# pcb.net
KiCad netlist of a schematic drawn in EAGLE
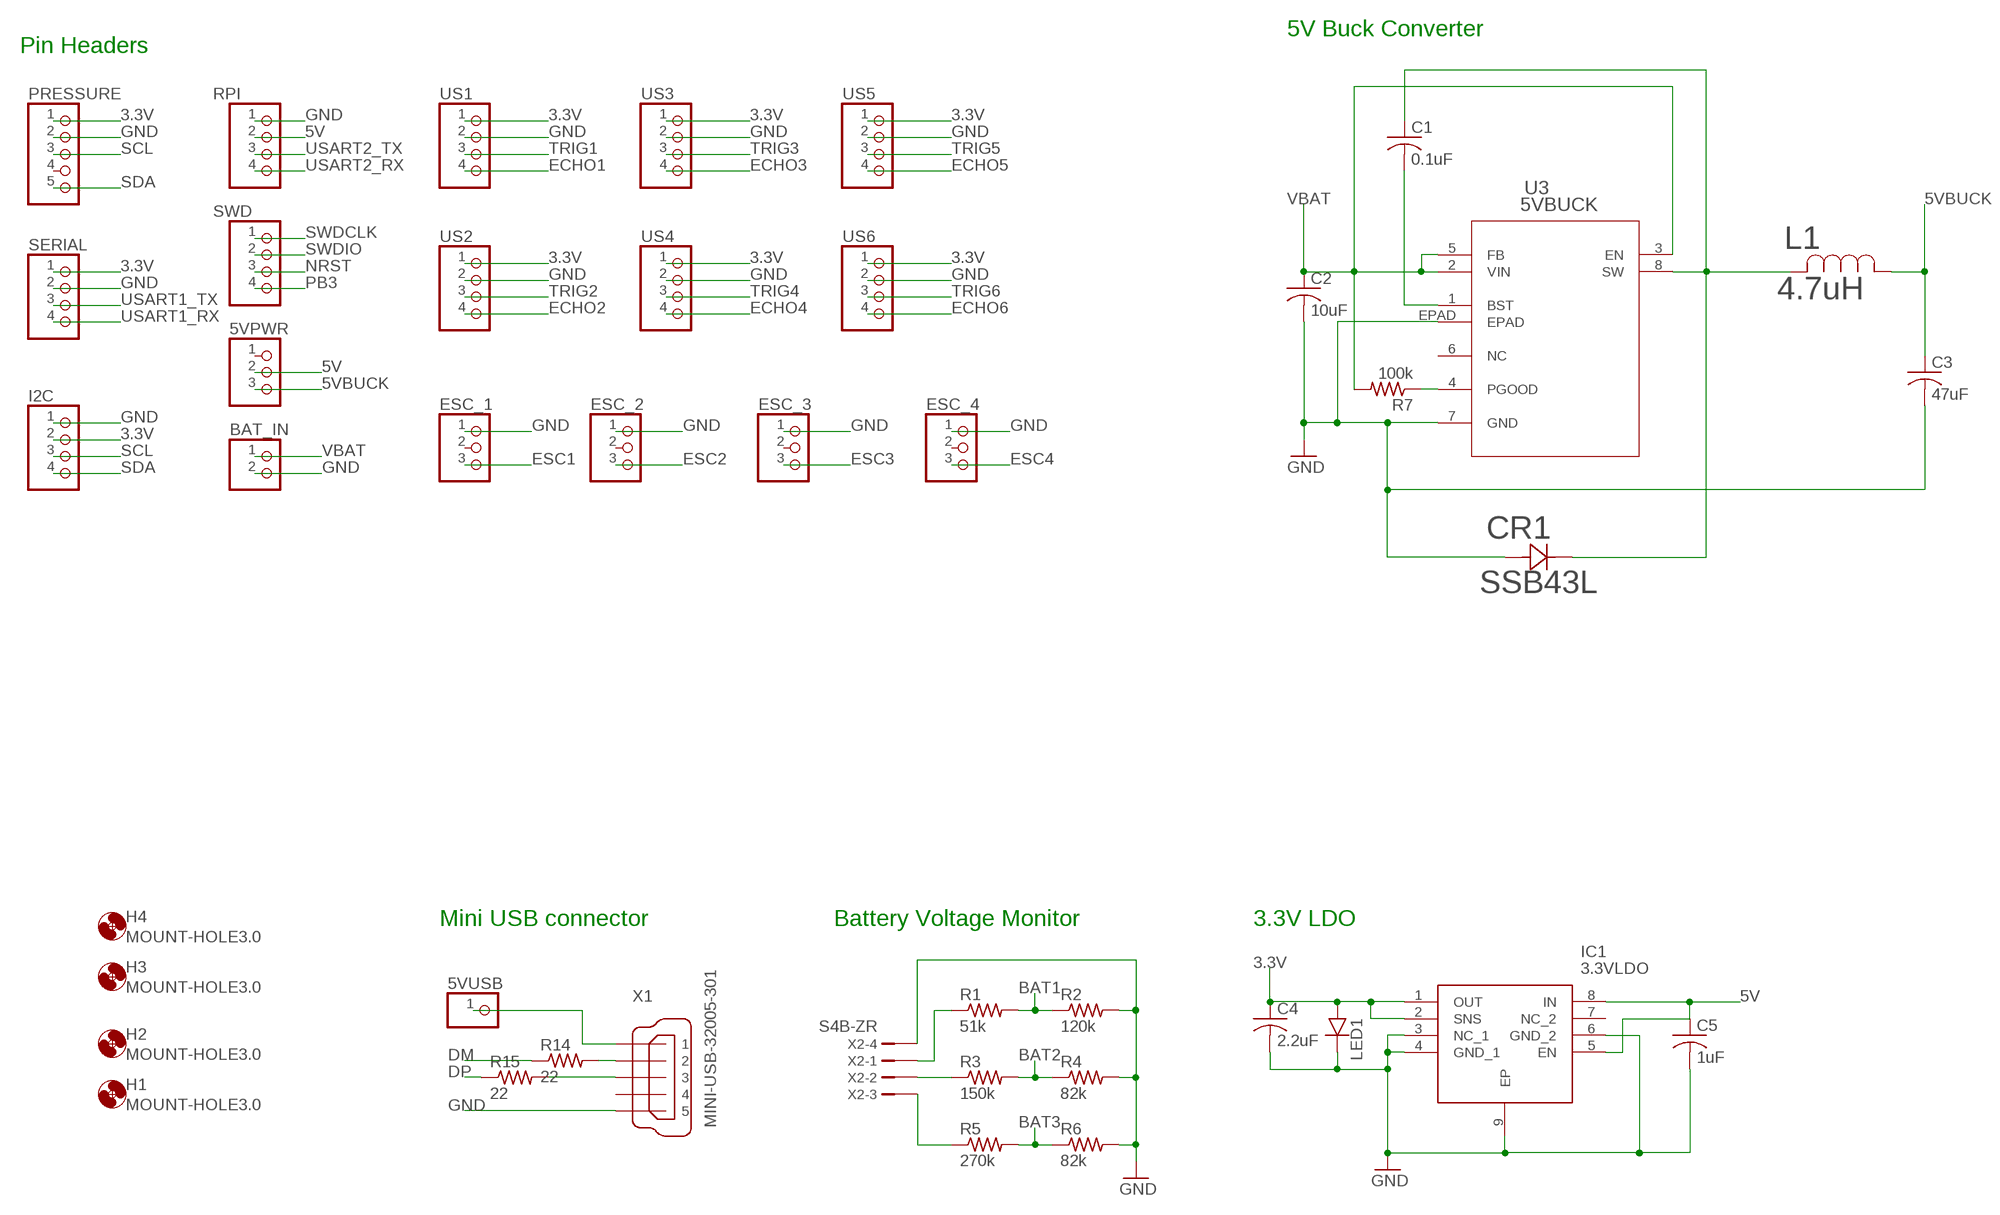
[diagram p0: schematic, sheet 1, part 1 of 2]
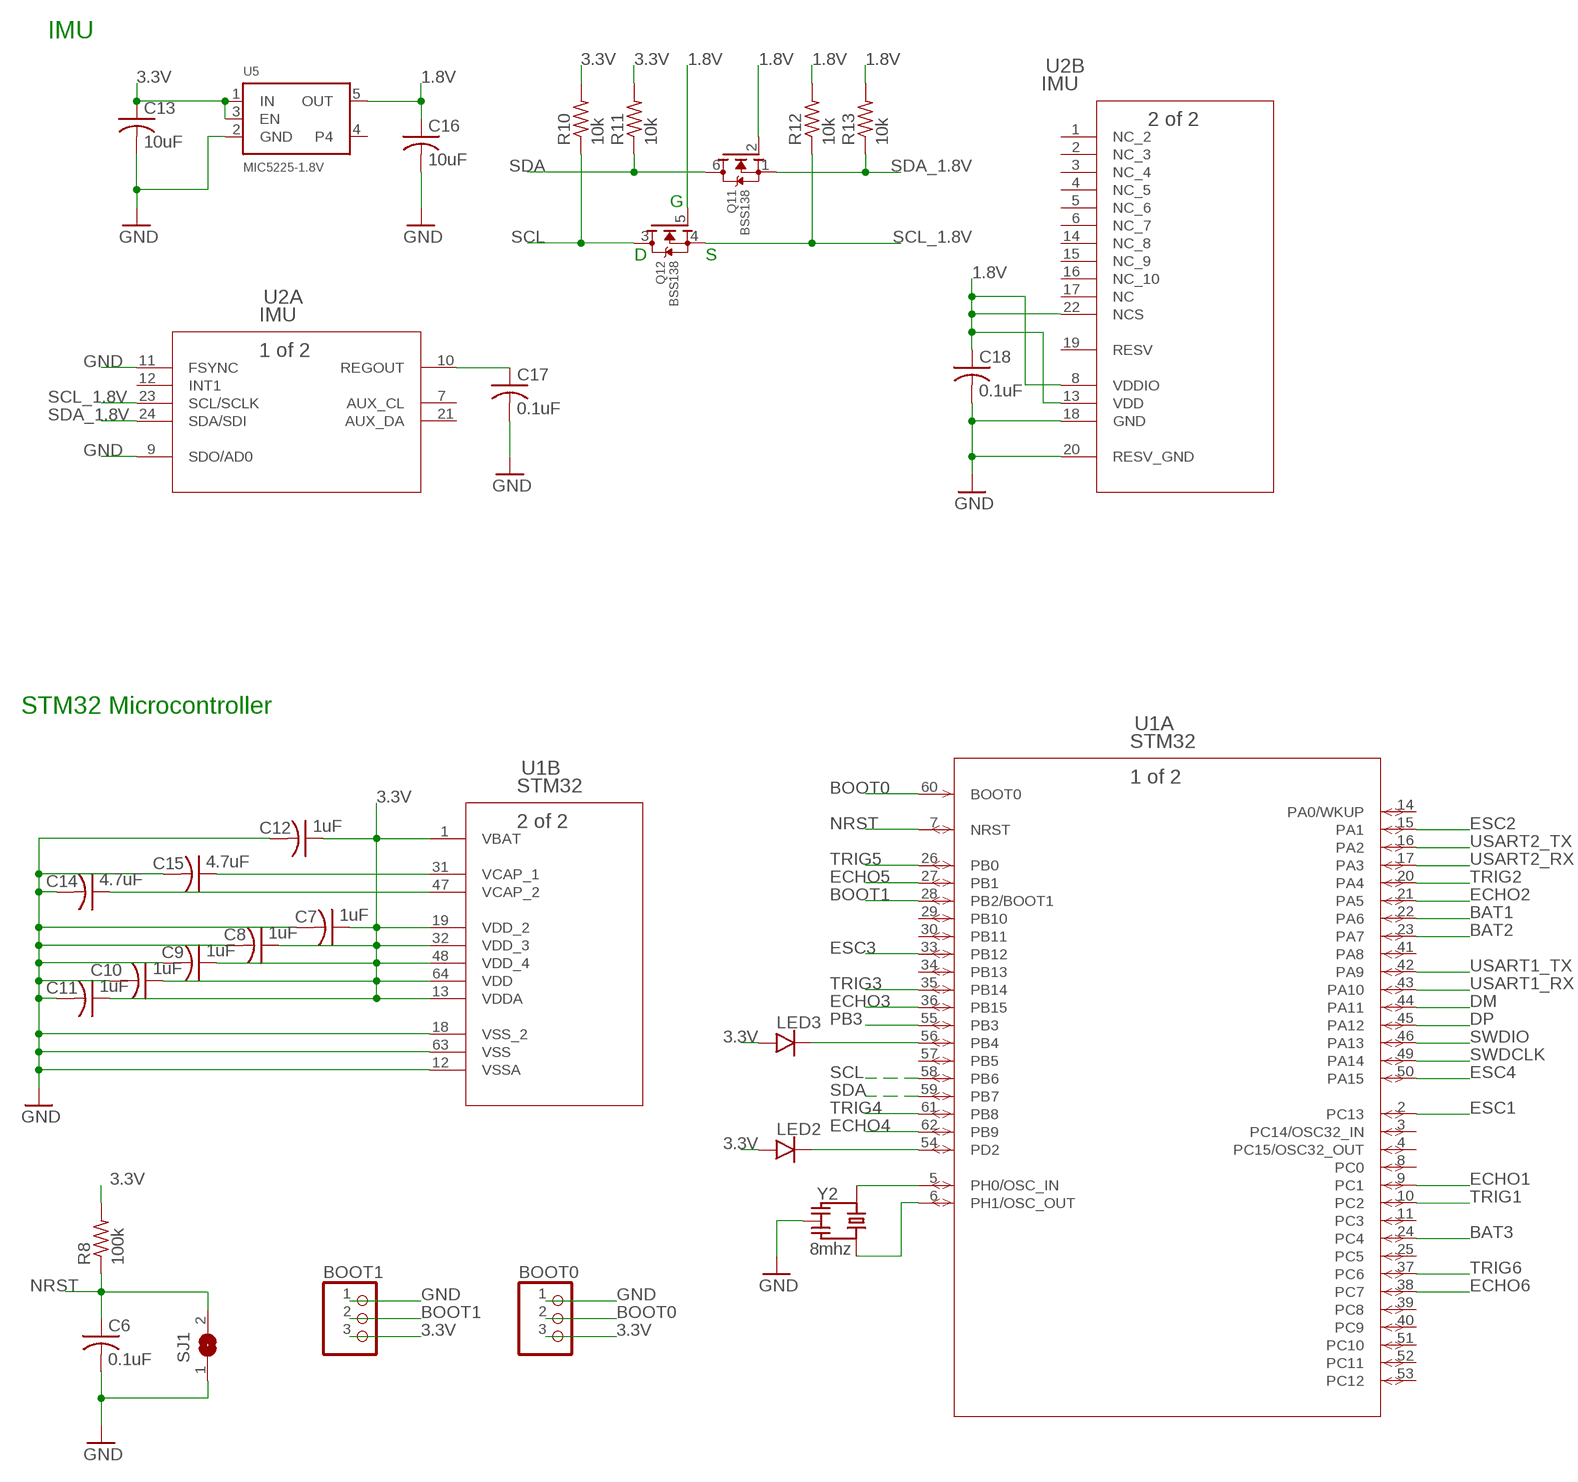
[diagram p1: schematic, sheet 1, part 2 of 2]

(export (version "E")
  (design (tool "Eeschema 10.0.6"))
  (components
    (comp (ref "5VPWR")
      (value "PINHD-1X3")
      (footprint "eagle-import:1X03")
      (libsource (lib "eagle-import") (part "PINHD-1X3"))
    )
    (comp (ref "5VUSB")
      (value "PINHD-1X1")
      (footprint "eagle-import:1X01")
      (libsource (lib "eagle-import") (part "PINHD-1X1"))
    )
    (comp (ref "BAT_IN")
      (value "PINHD-1X2")
      (footprint "eagle-import:1X02")
      (libsource (lib "eagle-import") (part "PINHD-1X2"))
    )
    (comp (ref "BOOT0")
      (value "PINHD-1X3")
      (footprint "eagle-import:1X03")
      (libsource (lib "eagle-import") (part "PINHD-1X3"))
    )
    (comp (ref "BOOT1")
      (value "PINHD-1X3")
      (footprint "eagle-import:1X03")
      (libsource (lib "eagle-import") (part "PINHD-1X3"))
    )
    (comp (ref "C1")
      (value "0.1uF")
      (footprint "eagle-import:C0805")
      (libsource (lib "eagle-import") (part "C-USC0805"))
    )
    (comp (ref "C2")
      (value "10uF")
      (footprint "eagle-import:C0805")
      (libsource (lib "eagle-import") (part "C-USC0805"))
    )
    (comp (ref "C3")
      (value "47uF")
      (footprint "eagle-import:C0805")
      (libsource (lib "eagle-import") (part "C-USC0805"))
    )
    (comp (ref "C4")
      (value "2.2uF")
      (footprint "eagle-import:C0805")
      (libsource (lib "eagle-import") (part "C-USC0805"))
    )
    (comp (ref "C5")
      (value "1uF")
      (footprint "eagle-import:C0805")
      (libsource (lib "eagle-import") (part "C-USC0805"))
    )
    (comp (ref "C6")
      (value "0.1uF")
      (footprint "eagle-import:C0805")
      (libsource (lib "eagle-import") (part "C-USC0805"))
    )
    (comp (ref "C7")
      (value "1uF")
      (footprint "eagle-import:C0805")
      (libsource (lib "eagle-import") (part "C-USC0805"))
    )
    (comp (ref "C8")
      (value "1uF")
      (footprint "eagle-import:C0805")
      (libsource (lib "eagle-import") (part "C-USC0805"))
    )
    (comp (ref "C9")
      (value "1uF")
      (footprint "eagle-import:C0805")
      (libsource (lib "eagle-import") (part "C-USC0805"))
    )
    (comp (ref "C10")
      (value "1uF")
      (footprint "eagle-import:C0805")
      (libsource (lib "eagle-import") (part "C-USC0805"))
    )
    (comp (ref "C11")
      (value "1uF")
      (footprint "eagle-import:C0805")
      (libsource (lib "eagle-import") (part "C-USC0805"))
    )
    (comp (ref "C12")
      (value "1uF")
      (footprint "eagle-import:C0805")
      (libsource (lib "eagle-import") (part "C-USC0805"))
    )
    (comp (ref "C13")
      (value "10uF")
      (footprint "eagle-import:C0805")
      (libsource (lib "eagle-import") (part "C-USC0805"))
    )
    (comp (ref "C14")
      (value "4.7uF")
      (footprint "eagle-import:C0805")
      (libsource (lib "eagle-import") (part "C-USC0805"))
    )
    (comp (ref "C15")
      (value "4.7uF")
      (footprint "eagle-import:C0805")
      (libsource (lib "eagle-import") (part "C-USC0805"))
    )
    (comp (ref "C16")
      (value "10uF")
      (footprint "eagle-import:C0805")
      (libsource (lib "eagle-import") (part "C-USC0805"))
    )
    (comp (ref "C17")
      (value "0.1uF")
      (footprint "eagle-import:C0805")
      (libsource (lib "eagle-import") (part "C-USC0805"))
    )
    (comp (ref "C18")
      (value "0.1uF")
      (footprint "eagle-import:C0805")
      (libsource (lib "eagle-import") (part "C-USC0805"))
    )
    (comp (ref "CR1")
      (value "SSB43L")
      (footprint "eagle-import:DIODE_DO214AA_MBRS-M")
      (fields (field (name "MANUFACTURER_PART_NUMBER") "SSB43L-E3/52T"))
      (libsource (lib "eagle-import") (part "SSB43L-E3/52TDIODE_DO214AA_MBRS-M"))
    )
    (comp (ref "ESC_1")
      (value "PINHD-1X3")
      (footprint "eagle-import:1X03")
      (libsource (lib "eagle-import") (part "PINHD-1X3"))
    )
    (comp (ref "ESC_2")
      (value "PINHD-1X3")
      (footprint "eagle-import:1X03")
      (libsource (lib "eagle-import") (part "PINHD-1X3"))
    )
    (comp (ref "ESC_3")
      (value "PINHD-1X3")
      (footprint "eagle-import:1X03")
      (libsource (lib "eagle-import") (part "PINHD-1X3"))
    )
    (comp (ref "ESC_4")
      (value "PINHD-1X3")
      (footprint "eagle-import:1X03")
      (libsource (lib "eagle-import") (part "PINHD-1X3"))
    )
    (comp (ref "H1")
      (value "MOUNT-HOLE3.0")
      (footprint "eagle-import:3,0")
      (libsource (lib "eagle-import") (part "MOUNT-HOLE3.0"))
    )
    (comp (ref "H2")
      (value "MOUNT-HOLE3.0")
      (footprint "eagle-import:3,0")
      (libsource (lib "eagle-import") (part "MOUNT-HOLE3.0"))
    )
    (comp (ref "H3")
      (value "MOUNT-HOLE3.0")
      (footprint "eagle-import:3,0")
      (libsource (lib "eagle-import") (part "MOUNT-HOLE3.0"))
    )
    (comp (ref "H4")
      (value "MOUNT-HOLE3.0")
      (footprint "eagle-import:3,0")
      (libsource (lib "eagle-import") (part "MOUNT-HOLE3.0"))
    )
    (comp (ref "I2C")
      (value "PINHD-1X4")
      (footprint "eagle-import:1X04")
      (libsource (lib "eagle-import") (part "PINHD-1X4"))
    )
    (comp (ref "IC1")
      (value "3.3VLDO")
      (footprint "eagle-import:SOP65P490X110-9N")
      (fields
        (field (name "MANUFACTURER_PART_NUMBER") "TLV76733DGNR")
        (field (name "MOUSER_PART_NUMBER") "595-TLV76733DGNR")
      )
      (libsource (lib "eagle-import") (part "TLV76733DGNR"))
    )
    (comp (ref "L1")
      (value "4.7uH")
      (footprint "eagle-import:IND_B82464G4_EPC")
      (fields (field (name "MANUFACTURER_PART_NUMBER") "B82464G4472M"))
      (libsource (lib "eagle-import") (part "B82464G4472M"))
    )
    (comp (ref "LED1")
      (value "SMD-CHIP-LED-0805")
      (footprint "eagle-import:SMD-CHIP-LED-0805")
      (fields (field (name "MF") "Kingbright") (field (name "MPN") "APHCM2012QBC/D-F01"))
      (libsource (lib "eagle-import") (part "SMD-CHIP-LED-0805"))
    )
    (comp (ref "LED2")
      (value "SMD-CHIP-LED-0805")
      (footprint "eagle-import:SMD-CHIP-LED-0805")
      (fields (field (name "MF") "Kingbright") (field (name "MPN") "APHCM2012QBC/D-F01"))
      (libsource (lib "eagle-import") (part "SMD-CHIP-LED-0805"))
    )
    (comp (ref "LED3")
      (value "SMD-CHIP-LED-0805")
      (footprint "eagle-import:SMD-CHIP-LED-0805")
      (fields (field (name "MF") "Kingbright") (field (name "MPN") "APHCM2012QBC/D-F01"))
      (libsource (lib "eagle-import") (part "SMD-CHIP-LED-0805"))
    )
    (comp (ref "PRESSURE")
      (value "PINHD-1X5")
      (footprint "eagle-import:1X05")
      (libsource (lib "eagle-import") (part "PINHD-1X5"))
    )
    (comp (ref "Q1")
      (value "BSS138")
      (footprint "eagle-import:SOT363")
      (libsource (lib "eagle-import") (part "MOSFET-N_DUAL"))
    )
    (comp (ref "R1")
      (value "51k")
      (footprint "eagle-import:R0805")
      (libsource (lib "eagle-import") (part "R-US_R0805"))
    )
    (comp (ref "R2")
      (value "120k")
      (footprint "eagle-import:R0805")
      (libsource (lib "eagle-import") (part "R-US_R0805"))
    )
    (comp (ref "R3")
      (value "150k")
      (footprint "eagle-import:R0805")
      (libsource (lib "eagle-import") (part "R-US_R0805"))
    )
    (comp (ref "R4")
      (value "82k")
      (footprint "eagle-import:R0805")
      (libsource (lib "eagle-import") (part "R-US_R0805"))
    )
    (comp (ref "R5")
      (value "270k")
      (footprint "eagle-import:R0805")
      (libsource (lib "eagle-import") (part "R-US_R0805"))
    )
    (comp (ref "R6")
      (value "82k")
      (footprint "eagle-import:R0805")
      (libsource (lib "eagle-import") (part "R-US_R0805"))
    )
    (comp (ref "R7")
      (value "100k")
      (footprint "eagle-import:R0805")
      (libsource (lib "eagle-import") (part "R-US_R0805"))
    )
    (comp (ref "R8")
      (value "100k")
      (footprint "eagle-import:R0805")
      (libsource (lib "eagle-import") (part "R-US_R0805"))
    )
    (comp (ref "R10")
      (value "10k")
      (footprint "eagle-import:R0805")
      (libsource (lib "eagle-import") (part "R-US_R0805"))
    )
    (comp (ref "R11")
      (value "10k")
      (footprint "eagle-import:R0805")
      (libsource (lib "eagle-import") (part "R-US_R0805"))
    )
    (comp (ref "R12")
      (value "10k")
      (footprint "eagle-import:R0805")
      (libsource (lib "eagle-import") (part "R-US_R0805"))
    )
    (comp (ref "R13")
      (value "10k")
      (footprint "eagle-import:R0805")
      (libsource (lib "eagle-import") (part "R-US_R0805"))
    )
    (comp (ref "R14")
      (value "22")
      (footprint "eagle-import:R0805")
      (libsource (lib "eagle-import") (part "R-US_R0805"))
    )
    (comp (ref "R15")
      (value "22")
      (footprint "eagle-import:R0805")
      (libsource (lib "eagle-import") (part "R-US_R0805"))
    )
    (comp (ref "RPI")
      (value "PINHD-1X4")
      (footprint "eagle-import:1X04")
      (libsource (lib "eagle-import") (part "PINHD-1X4"))
    )
    (comp (ref "SERIAL")
      (value "PINHD-1X4")
      (footprint "eagle-import:1X04")
      (libsource (lib "eagle-import") (part "PINHD-1X4"))
    )
    (comp (ref "SJ1") (value "SJ") (footprint "eagle-import:SJ") (libsource (lib "eagle-import") (part "SJ")))
    (comp (ref "SWD")
      (value "PINHD-1X4")
      (footprint "eagle-import:1X04")
      (libsource (lib "eagle-import") (part "PINHD-1X4"))
    )
    (comp (ref "U1")
      (value "STM32")
      (footprint "eagle-import:LQFP64-10X10MM")
      (fields
        (field (name "MANUFACTURER_PART_NUMBER") "STM32F405RGT6W")
        (field (name "COPYRIGHT") "Copyright (C) 2018 Accelerated Designs. All rights reserved")
      )
      (libsource (lib "eagle-import") (part "STM32F405RGT6W"))
    )
    (comp (ref "U2")
      (value "IMU")
      (footprint "eagle-import:QFN24_3X3X0P9_IVS")
      (fields
        (field (name "MANUFACTURER_PART_NUMBER") "ICM-20948")
        (field (name "COPYRIGHT") "Copyright (C) 2018 Accelerated Designs. All rights reserved")
      )
      (libsource (lib "eagle-import") (part "ICM-20948"))
    )
    (comp (ref "U3")
      (value "5VBUCK")
      (footprint "eagle-import:RD_8_1_ADI-M")
      (fields (field (name "MANUFACTURER_PART_NUMBER") "ADP2303ARDZ-5.0-R7"))
      (libsource (lib "eagle-import") (part "ADP2303ARDZ-5.0-R7RD_8_1_ADI-M"))
    )
    (comp (ref "U5")
      (value "MIC5225-1.8V")
      (footprint "eagle-import:SOT23-5")
      (libsource (lib "eagle-import") (part "VREG_SOT23-5"))
    )
    (comp (ref "US1")
      (value "PINHD-1X4")
      (footprint "eagle-import:1X04")
      (libsource (lib "eagle-import") (part "PINHD-1X4"))
    )
    (comp (ref "US2")
      (value "PINHD-1X4")
      (footprint "eagle-import:1X04")
      (libsource (lib "eagle-import") (part "PINHD-1X4"))
    )
    (comp (ref "US3")
      (value "PINHD-1X4")
      (footprint "eagle-import:1X04")
      (libsource (lib "eagle-import") (part "PINHD-1X4"))
    )
    (comp (ref "US4")
      (value "PINHD-1X4")
      (footprint "eagle-import:1X04")
      (libsource (lib "eagle-import") (part "PINHD-1X4"))
    )
    (comp (ref "US5")
      (value "PINHD-1X4")
      (footprint "eagle-import:1X04")
      (libsource (lib "eagle-import") (part "PINHD-1X4"))
    )
    (comp (ref "US6")
      (value "PINHD-1X4")
      (footprint "eagle-import:1X04")
      (libsource (lib "eagle-import") (part "PINHD-1X4"))
    )
    (comp (ref "X1")
      (value "MINI-USB-32005-301")
      (footprint "eagle-import:32005-301")
      (libsource (lib "eagle-import") (part "MINI-USB-32005-301"))
    )
    (comp (ref "X2")
      (value "S4B-ZR")
      (footprint "eagle-import:S4B-ZR")
      (fields (field (name "MF") "FARNELL") (field (name "MPN") "S4B-ZR(LF)(SN)"))
      (libsource (lib "eagle-import") (part "?4B-ZRS"))
    )
    (comp (ref "Y2")
      (value "8mhz")
      (footprint "eagle-import:RESONATOR_8")
      (fields (field (name "MF") "Murata") (field (name "MPN") "CSTCE8M00G55-R0"))
      (libsource (lib "eagle-import") (part "RESONATOR8MHZ"))
    )
  )
  (nets
    (net (code "1") (name "/1.8V") (class "Default")
      (node (ref "C16") (pin "1") (pinfunction "1_1") (pintype "passive"))
      (node (ref "C18") (pin "1") (pinfunction "1_1") (pintype "passive"))
      (node (ref "Q1") (pin "2") (pinfunction "G_2") (pintype "bidirectional"))
      (node (ref "Q1") (pin "5") (pinfunction "G_5") (pintype "bidirectional"))
      (node (ref "R12") (pin "2") (pinfunction "2_2") (pintype "passive"))
      (node (ref "R13") (pin "2") (pinfunction "2_2") (pintype "passive"))
      (node (ref "U2") (pin "13") (pinfunction "VDD_13") (pintype "power_in"))
      (node (ref "U2") (pin "22") (pinfunction "NCS_22") (pintype "input"))
      (node (ref "U2") (pin "8") (pinfunction "VDDIO_8") (pintype "power_in"))
      (node (ref "U5") (pin "5") (pinfunction "OUT_5") (pintype "power_in"))
    )
    (net (code "2") (name "/3.3V") (class "Default")
      (node (ref "BOOT0") (pin "3") (pinfunction "3_3") (pintype "passive"))
      (node (ref "BOOT1") (pin "3") (pinfunction "3_3") (pintype "passive"))
      (node (ref "C10") (pin "1") (pinfunction "1_1") (pintype "passive"))
      (node (ref "C11") (pin "1") (pinfunction "1_1") (pintype "passive"))
      (node (ref "C12") (pin "1") (pinfunction "1_1") (pintype "passive"))
      (node (ref "C13") (pin "1") (pinfunction "1_1") (pintype "passive"))
      (node (ref "C4") (pin "1") (pinfunction "1_1") (pintype "passive"))
      (node (ref "C7") (pin "1") (pinfunction "1_1") (pintype "passive"))
      (node (ref "C8") (pin "1") (pinfunction "1_1") (pintype "passive"))
      (node (ref "C9") (pin "1") (pinfunction "1_1") (pintype "passive"))
      (node (ref "I2C") (pin "2") (pinfunction "2_2") (pintype "passive"))
      (node (ref "IC1") (pin "1") (pinfunction "OUT_1") (pintype "bidirectional"))
      (node (ref "IC1") (pin "2") (pinfunction "SNS_2") (pintype "bidirectional"))
      (node (ref "LED1") (pin "A") (pinfunction "A_A") (pintype "passive"))
      (node (ref "LED2") (pin "A") (pinfunction "A_A") (pintype "passive"))
      (node (ref "LED3") (pin "A") (pinfunction "A_A") (pintype "passive"))
      (node (ref "PRESSURE") (pin "1") (pinfunction "1_1") (pintype "passive"))
      (node (ref "R10") (pin "2") (pinfunction "2_2") (pintype "passive"))
      (node (ref "R11") (pin "2") (pinfunction "2_2") (pintype "passive"))
      (node (ref "R8") (pin "2") (pinfunction "2_2") (pintype "passive"))
      (node (ref "SERIAL") (pin "1") (pinfunction "1_1") (pintype "passive"))
      (node (ref "U1") (pin "1") (pinfunction "VBAT_1") (pintype "power_in"))
      (node (ref "U1") (pin "13") (pinfunction "VDDA_13") (pintype "power_in"))
      (node (ref "U1") (pin "19") (pinfunction "VDD_2_19") (pintype "power_in"))
      (node (ref "U1") (pin "32") (pinfunction "VDD_3_32") (pintype "power_in"))
      (node (ref "U1") (pin "48") (pinfunction "VDD_4_48") (pintype "power_in"))
      (node (ref "U1") (pin "64") (pinfunction "VDD_64") (pintype "power_in"))
      (node (ref "U5") (pin "1") (pinfunction "IN_1") (pintype "power_in"))
      (node (ref "U5") (pin "3") (pinfunction "EN_3") (pintype "input"))
      (node (ref "US1") (pin "1") (pinfunction "1_1") (pintype "passive"))
      (node (ref "US2") (pin "1") (pinfunction "1_1") (pintype "passive"))
      (node (ref "US3") (pin "1") (pinfunction "1_1") (pintype "passive"))
      (node (ref "US4") (pin "1") (pinfunction "1_1") (pintype "passive"))
      (node (ref "US5") (pin "1") (pinfunction "1_1") (pintype "passive"))
      (node (ref "US6") (pin "1") (pinfunction "1_1") (pintype "passive"))
    )
    (net (code "3") (name "/5V") (class "Default")
      (node (ref "5VPWR") (pin "2") (pinfunction "2_2") (pintype "passive"))
      (node (ref "C5") (pin "1") (pinfunction "1_1") (pintype "passive"))
      (node (ref "IC1") (pin "5") (pinfunction "EN_5") (pintype "bidirectional"))
      (node (ref "IC1") (pin "8") (pinfunction "IN_8") (pintype "bidirectional"))
      (node (ref "RPI") (pin "2") (pinfunction "2_2") (pintype "passive"))
    )
    (net (code "4") (name "/5VBUCK") (class "Default")
      (node (ref "5VPWR") (pin "3") (pinfunction "3_3") (pintype "passive"))
      (node (ref "C3") (pin "1") (pinfunction "1_1") (pintype "passive"))
      (node (ref "L1") (pin "1") (pinfunction "1_1") (pintype "passive"))
    )
    (net (code "5") (name "/BAT1") (class "Default")
      (node (ref "R1") (pin "2") (pinfunction "2_2") (pintype "passive"))
      (node (ref "R2") (pin "1") (pinfunction "1_1") (pintype "passive"))
      (node (ref "U1") (pin "22") (pinfunction "PA6_22") (pintype "bidirectional"))
    )
    (net (code "6") (name "/BAT2") (class "Default")
      (node (ref "R3") (pin "2") (pinfunction "2_2") (pintype "passive"))
      (node (ref "R4") (pin "1") (pinfunction "1_1") (pintype "passive"))
      (node (ref "U1") (pin "23") (pinfunction "PA7_23") (pintype "bidirectional"))
    )
    (net (code "7") (name "/BAT3") (class "Default")
      (node (ref "R5") (pin "2") (pinfunction "2_2") (pintype "passive"))
      (node (ref "R6") (pin "1") (pinfunction "1_1") (pintype "passive"))
      (node (ref "U1") (pin "24") (pinfunction "PC4_24") (pintype "bidirectional"))
    )
    (net (code "8") (name "/BOOT0") (class "Default")
      (node (ref "BOOT0") (pin "2") (pinfunction "2_2") (pintype "passive"))
      (node (ref "U1") (pin "60") (pinfunction "BOOT0_60") (pintype "input"))
    )
    (net (code "9") (name "/BOOT1") (class "Default")
      (node (ref "BOOT1") (pin "2") (pinfunction "2_2") (pintype "passive"))
      (node (ref "U1") (pin "28") (pinfunction "PB2/BOOT1_28") (pintype "bidirectional"))
    )
    (net (code "10") (name "/DM") (class "Default")
      (node (ref "R14") (pin "1") (pinfunction "1_1") (pintype "passive"))
      (node (ref "U1") (pin "44") (pinfunction "PA11_44") (pintype "bidirectional"))
    )
    (net (code "11") (name "/DP") (class "Default")
      (node (ref "R15") (pin "1") (pinfunction "1_1") (pintype "passive"))
      (node (ref "U1") (pin "45") (pinfunction "PA12_45") (pintype "bidirectional"))
    )
    (net (code "12") (name "/ECHO1") (class "Default")
      (node (ref "U1") (pin "9") (pinfunction "PC1_9") (pintype "bidirectional"))
      (node (ref "US1") (pin "4") (pinfunction "4_4") (pintype "passive"))
    )
    (net (code "13") (name "/ECHO2") (class "Default")
      (node (ref "U1") (pin "21") (pinfunction "PA5_21") (pintype "bidirectional"))
      (node (ref "US2") (pin "4") (pinfunction "4_4") (pintype "passive"))
    )
    (net (code "14") (name "/ECHO3") (class "Default")
      (node (ref "U1") (pin "36") (pinfunction "PB15_36") (pintype "bidirectional"))
      (node (ref "US3") (pin "4") (pinfunction "4_4") (pintype "passive"))
    )
    (net (code "15") (name "/ECHO4") (class "Default")
      (node (ref "U1") (pin "62") (pinfunction "PB9_62") (pintype "bidirectional"))
      (node (ref "US4") (pin "4") (pinfunction "4_4") (pintype "passive"))
    )
    (net (code "16") (name "/ECHO5") (class "Default")
      (node (ref "U1") (pin "27") (pinfunction "PB1_27") (pintype "bidirectional"))
      (node (ref "US5") (pin "4") (pinfunction "4_4") (pintype "passive"))
    )
    (net (code "17") (name "/ECHO6") (class "Default")
      (node (ref "U1") (pin "38") (pinfunction "PC7_38") (pintype "bidirectional"))
      (node (ref "US6") (pin "4") (pinfunction "4_4") (pintype "passive"))
    )
    (net (code "18") (name "/ESC1") (class "Default")
      (node (ref "ESC_1") (pin "3") (pinfunction "3_3") (pintype "passive"))
      (node (ref "U1") (pin "2") (pinfunction "PC13_2") (pintype "bidirectional"))
    )
    (net (code "19") (name "/ESC2") (class "Default")
      (node (ref "ESC_2") (pin "3") (pinfunction "3_3") (pintype "passive"))
      (node (ref "U1") (pin "15") (pinfunction "PA1_15") (pintype "bidirectional"))
    )
    (net (code "20") (name "/ESC3") (class "Default")
      (node (ref "ESC_3") (pin "3") (pinfunction "3_3") (pintype "passive"))
      (node (ref "U1") (pin "33") (pinfunction "PB12_33") (pintype "bidirectional"))
    )
    (net (code "21") (name "/ESC4") (class "Default")
      (node (ref "ESC_4") (pin "3") (pinfunction "3_3") (pintype "passive"))
      (node (ref "U1") (pin "50") (pinfunction "PA15_50") (pintype "bidirectional"))
    )
    (net (code "22") (name "/NRST") (class "Default")
      (node (ref "C6") (pin "1") (pinfunction "1_1") (pintype "passive"))
      (node (ref "R8") (pin "1") (pinfunction "1_1") (pintype "passive"))
      (node (ref "SJ1") (pin "2") (pinfunction "2_2") (pintype "passive"))
      (node (ref "SWD") (pin "3") (pinfunction "3_3") (pintype "passive"))
      (node (ref "U1") (pin "7") (pinfunction "NRST_7") (pintype "bidirectional"))
    )
    (net (code "23") (name "/PB3") (class "Default")
      (node (ref "SWD") (pin "4") (pinfunction "4_4") (pintype "passive"))
      (node (ref "U1") (pin "55") (pinfunction "PB3_55") (pintype "bidirectional"))
    )
    (net (code "24") (name "/SCL") (class "Default")
      (node (ref "I2C") (pin "3") (pinfunction "3_3") (pintype "passive"))
      (node (ref "PRESSURE") (pin "3") (pinfunction "3_3") (pintype "passive"))
      (node (ref "Q1") (pin "3") (pinfunction "D_3") (pintype "bidirectional"))
      (node (ref "R10") (pin "1") (pinfunction "1_1") (pintype "passive"))
      (node (ref "U1") (pin "58") (pinfunction "PB6_58") (pintype "bidirectional"))
    )
    (net (code "25") (name "/SCL_1.8V") (class "Default")
      (node (ref "Q1") (pin "4") (pinfunction "S_4") (pintype "bidirectional"))
      (node (ref "R12") (pin "1") (pinfunction "1_1") (pintype "passive"))
      (node (ref "U2") (pin "23") (pinfunction "SCL/SCLK_23") (pintype "input"))
    )
    (net (code "26") (name "/SDA") (class "Default")
      (node (ref "I2C") (pin "4") (pinfunction "4_4") (pintype "passive"))
      (node (ref "PRESSURE") (pin "5") (pinfunction "5_5") (pintype "passive"))
      (node (ref "Q1") (pin "6") (pinfunction "D_6") (pintype "bidirectional"))
      (node (ref "R11") (pin "1") (pinfunction "1_1") (pintype "passive"))
      (node (ref "U1") (pin "59") (pinfunction "PB7_59") (pintype "bidirectional"))
    )
    (net (code "27") (name "/SDA_1.8V") (class "Default")
      (node (ref "Q1") (pin "1") (pinfunction "S_1") (pintype "bidirectional"))
      (node (ref "R13") (pin "1") (pinfunction "1_1") (pintype "passive"))
      (node (ref "U2") (pin "24") (pinfunction "SDA/SDI_24") (pintype "input"))
    )
    (net (code "28") (name "/SWDCLK") (class "Default")
      (node (ref "SWD") (pin "1") (pinfunction "1_1") (pintype "passive"))
      (node (ref "U1") (pin "49") (pinfunction "PA14_49") (pintype "bidirectional"))
    )
    (net (code "29") (name "/SWDIO") (class "Default")
      (node (ref "SWD") (pin "2") (pinfunction "2_2") (pintype "passive"))
      (node (ref "U1") (pin "46") (pinfunction "PA13_46") (pintype "bidirectional"))
    )
    (net (code "30") (name "/TRIG1") (class "Default")
      (node (ref "U1") (pin "10") (pinfunction "PC2_10") (pintype "bidirectional"))
      (node (ref "US1") (pin "3") (pinfunction "3_3") (pintype "passive"))
    )
    (net (code "31") (name "/TRIG2") (class "Default")
      (node (ref "U1") (pin "20") (pinfunction "PA4_20") (pintype "bidirectional"))
      (node (ref "US2") (pin "3") (pinfunction "3_3") (pintype "passive"))
    )
    (net (code "32") (name "/TRIG3") (class "Default")
      (node (ref "U1") (pin "35") (pinfunction "PB14_35") (pintype "bidirectional"))
      (node (ref "US3") (pin "3") (pinfunction "3_3") (pintype "passive"))
    )
    (net (code "33") (name "/TRIG4") (class "Default")
      (node (ref "U1") (pin "61") (pinfunction "PB8_61") (pintype "bidirectional"))
      (node (ref "US4") (pin "3") (pinfunction "3_3") (pintype "passive"))
    )
    (net (code "34") (name "/TRIG5") (class "Default")
      (node (ref "U1") (pin "26") (pinfunction "PB0_26") (pintype "bidirectional"))
      (node (ref "US5") (pin "3") (pinfunction "3_3") (pintype "passive"))
    )
    (net (code "35") (name "/TRIG6") (class "Default")
      (node (ref "U1") (pin "37") (pinfunction "PC6_37") (pintype "bidirectional"))
      (node (ref "US6") (pin "3") (pinfunction "3_3") (pintype "passive"))
    )
    (net (code "36") (name "/USART1_RX") (class "Default")
      (node (ref "SERIAL") (pin "4") (pinfunction "4_4") (pintype "passive"))
      (node (ref "U1") (pin "43") (pinfunction "PA10_43") (pintype "bidirectional"))
    )
    (net (code "37") (name "/USART1_TX") (class "Default")
      (node (ref "SERIAL") (pin "3") (pinfunction "3_3") (pintype "passive"))
      (node (ref "U1") (pin "42") (pinfunction "PA9_42") (pintype "bidirectional"))
    )
    (net (code "38") (name "/USART2_RX") (class "Default")
      (node (ref "RPI") (pin "4") (pinfunction "4_4") (pintype "passive"))
      (node (ref "U1") (pin "17") (pinfunction "PA3_17") (pintype "bidirectional"))
    )
    (net (code "39") (name "/USART2_TX") (class "Default")
      (node (ref "RPI") (pin "3") (pinfunction "3_3") (pintype "passive"))
      (node (ref "U1") (pin "16") (pinfunction "PA2_16") (pintype "bidirectional"))
    )
    (net (code "40") (name "/VBAT") (class "Default")
      (node (ref "BAT_IN") (pin "1") (pinfunction "1_1") (pintype "passive"))
      (node (ref "C2") (pin "1") (pinfunction "1_1") (pintype "passive"))
      (node (ref "R7") (pin "2") (pinfunction "2_2") (pintype "passive"))
      (node (ref "U3") (pin "2") (pinfunction "VIN_2") (pintype "input"))
      (node (ref "U3") (pin "3") (pinfunction "EN_3") (pintype "output"))
      (node (ref "U3") (pin "5") (pinfunction "FB_5") (pintype "input"))
    )
    (net (code "41") (name "GND") (class "Default")
      (node (ref "BAT_IN") (pin "2") (pinfunction "2_2") (pintype "passive"))
      (node (ref "BOOT0") (pin "1") (pinfunction "1_1") (pintype "passive"))
      (node (ref "BOOT1") (pin "1") (pinfunction "1_1") (pintype "passive"))
      (node (ref "C10") (pin "2") (pinfunction "2_2") (pintype "passive"))
      (node (ref "C11") (pin "2") (pinfunction "2_2") (pintype "passive"))
      (node (ref "C12") (pin "2") (pinfunction "2_2") (pintype "passive"))
      (node (ref "C13") (pin "2") (pinfunction "2_2") (pintype "passive"))
      (node (ref "C14") (pin "2") (pinfunction "2_2") (pintype "passive"))
      (node (ref "C15") (pin "2") (pinfunction "2_2") (pintype "passive"))
      (node (ref "C16") (pin "2") (pinfunction "2_2") (pintype "passive"))
      (node (ref "C17") (pin "2") (pinfunction "2_2") (pintype "passive"))
      (node (ref "C18") (pin "2") (pinfunction "2_2") (pintype "passive"))
      (node (ref "C2") (pin "2") (pinfunction "2_2") (pintype "passive"))
      (node (ref "C3") (pin "2") (pinfunction "2_2") (pintype "passive"))
      (node (ref "C4") (pin "2") (pinfunction "2_2") (pintype "passive"))
      (node (ref "C5") (pin "2") (pinfunction "2_2") (pintype "passive"))
      (node (ref "C6") (pin "2") (pinfunction "2_2") (pintype "passive"))
      (node (ref "C7") (pin "2") (pinfunction "2_2") (pintype "passive"))
      (node (ref "C8") (pin "2") (pinfunction "2_2") (pintype "passive"))
      (node (ref "C9") (pin "2") (pinfunction "2_2") (pintype "passive"))
      (node (ref "CR1") (pin "2") (pinfunction "2_2") (pintype "passive"))
      (node (ref "ESC_1") (pin "1") (pinfunction "1_1") (pintype "passive"))
      (node (ref "ESC_2") (pin "1") (pinfunction "1_1") (pintype "passive"))
      (node (ref "ESC_3") (pin "1") (pinfunction "1_1") (pintype "passive"))
      (node (ref "ESC_4") (pin "1") (pinfunction "1_1") (pintype "passive"))
      (node (ref "I2C") (pin "1") (pinfunction "1_1") (pintype "passive"))
      (node (ref "IC1") (pin "3") (pinfunction "NC_1_3") (pintype "bidirectional"))
      (node (ref "IC1") (pin "4") (pinfunction "GND_1_4") (pintype "bidirectional"))
      (node (ref "IC1") (pin "6") (pinfunction "GND_2_6") (pintype "bidirectional"))
      (node (ref "IC1") (pin "9") (pinfunction "EP_9") (pintype "bidirectional"))
      (node (ref "LED1") (pin "C") (pinfunction "C_C") (pintype "passive"))
      (node (ref "PRESSURE") (pin "2") (pinfunction "2_2") (pintype "passive"))
      (node (ref "R2") (pin "2") (pinfunction "2_2") (pintype "passive"))
      (node (ref "R4") (pin "2") (pinfunction "2_2") (pintype "passive"))
      (node (ref "R6") (pin "2") (pinfunction "2_2") (pintype "passive"))
      (node (ref "RPI") (pin "1") (pinfunction "1_1") (pintype "passive"))
      (node (ref "SERIAL") (pin "2") (pinfunction "2_2") (pintype "passive"))
      (node (ref "SJ1") (pin "1") (pinfunction "1_1") (pintype "passive"))
      (node (ref "U1") (pin "12") (pinfunction "VSSA_12") (pintype "power_in"))
      (node (ref "U1") (pin "18") (pinfunction "VSS_2_18") (pintype "power_in"))
      (node (ref "U1") (pin "63") (pinfunction "VSS_63") (pintype "power_in"))
      (node (ref "U2") (pin "11") (pinfunction "FSYNC_11") (pintype "input"))
      (node (ref "U2") (pin "18") (pinfunction "GND_18") (pintype "passive"))
      (node (ref "U2") (pin "20") (pinfunction "RESV_GND_20") (pintype "passive"))
      (node (ref "U2") (pin "9") (pinfunction "SDO/AD0_9") (pintype "bidirectional"))
      (node (ref "U3") (pin "7") (pinfunction "GND_7") (pintype "power_in"))
      (node (ref "U3") (pin "EPAD") (pinfunction "EPAD_EPAD") (pintype "passive"))
      (node (ref "U5") (pin "2") (pinfunction "GND_2") (pintype "power_in"))
      (node (ref "US1") (pin "2") (pinfunction "2_2") (pintype "passive"))
      (node (ref "US2") (pin "2") (pinfunction "2_2") (pintype "passive"))
      (node (ref "US3") (pin "2") (pinfunction "2_2") (pintype "passive"))
      (node (ref "US4") (pin "2") (pinfunction "2_2") (pintype "passive"))
      (node (ref "US5") (pin "2") (pinfunction "2_2") (pintype "passive"))
      (node (ref "US6") (pin "2") (pinfunction "2_2") (pintype "passive"))
      (node (ref "X1") (pin "5") (pinfunction "5_5") (pintype "passive"))
      (node (ref "X2") (pin "4") (pinfunction "1_4") (pintype "passive"))
      (node (ref "Y2") (pin "2") (pinfunction "2_2") (pintype "passive"))
    )
    (net (code "42") (name "Net-(5VUSB-Pad1)") (class "Default")
      (node (ref "5VUSB") (pin "1") (pinfunction "1_1") (pintype "passive"))
      (node (ref "X1") (pin "1") (pinfunction "1_1") (pintype "passive"))
    )
    (net (code "43") (name "Net-(R1-Pad1)") (class "Default")
      (node (ref "R1") (pin "1") (pinfunction "1_1") (pintype "passive"))
      (node (ref "X2") (pin "1") (pinfunction "1_1") (pintype "passive"))
    )
    (net (code "44") (name "Net-(R14-Pad2)") (class "Default")
      (node (ref "R14") (pin "2") (pinfunction "2_2") (pintype "passive"))
      (node (ref "X1") (pin "2") (pinfunction "2_2") (pintype "passive"))
    )
    (net (code "45") (name "Net-(R15-Pad2)") (class "Default")
      (node (ref "R15") (pin "2") (pinfunction "2_2") (pintype "passive"))
      (node (ref "X1") (pin "3") (pinfunction "3_3") (pintype "passive"))
    )
    (net (code "46") (name "Net-(U1A-PB4)") (class "Default")
      (node (ref "LED3") (pin "C") (pinfunction "C_C") (pintype "passive"))
      (node (ref "U1") (pin "56") (pinfunction "PB4_56") (pintype "bidirectional"))
    )
    (net (code "47") (name "Net-(U1A-PD2)") (class "Default")
      (node (ref "LED2") (pin "C") (pinfunction "C_C") (pintype "passive"))
      (node (ref "U1") (pin "54") (pinfunction "PD2_54") (pintype "bidirectional"))
    )
    (net (code "48") (name "Net-(U1A-PH0{slash}OSC_IN)") (class "Default")
      (node (ref "U1") (pin "5") (pinfunction "PH0/OSC_IN_5") (pintype "bidirectional"))
      (node (ref "Y2") (pin "1") (pinfunction "1_1") (pintype "passive"))
    )
    (net (code "49") (name "Net-(U1A-PH1{slash}OSC_OUT)") (class "Default")
      (node (ref "U1") (pin "6") (pinfunction "PH1/OSC_OUT_6") (pintype "bidirectional"))
      (node (ref "Y2") (pin "3") (pinfunction "3_3") (pintype "passive"))
    )
    (net (code "50") (name "Net-(U1B-VCAP_1)") (class "Default")
      (node (ref "C15") (pin "1") (pinfunction "1_1") (pintype "passive"))
      (node (ref "U1") (pin "31") (pinfunction "VCAP_1_31") (pintype "power_in"))
    )
    (net (code "51") (name "Net-(U1B-VCAP_2)") (class "Default")
      (node (ref "C14") (pin "1") (pinfunction "1_1") (pintype "passive"))
      (node (ref "U1") (pin "47") (pinfunction "VCAP_2_47") (pintype "power_in"))
    )
    (net (code "52") (name "Net-(U2A-REGOUT)") (class "Default")
      (node (ref "C17") (pin "1") (pinfunction "1_1") (pintype "passive"))
      (node (ref "U2") (pin "10") (pinfunction "REGOUT_10") (pintype "output"))
    )
    (net (code "53") (name "Net-(U3-BST)") (class "Default")
      (node (ref "C1") (pin "2") (pinfunction "2_2") (pintype "passive"))
      (node (ref "U3") (pin "1") (pinfunction "BST_1") (pintype "passive"))
    )
    (net (code "54") (name "Net-(U3-PGOOD)") (class "Default")
      (node (ref "R7") (pin "1") (pinfunction "1_1") (pintype "passive"))
      (node (ref "U3") (pin "4") (pinfunction "PGOOD_4") (pintype "output"))
    )
    (net (code "55") (name "Net-(U3-SW)") (class "Default")
      (node (ref "C1") (pin "1") (pinfunction "1_1") (pintype "passive"))
      (node (ref "CR1") (pin "1") (pinfunction "1_1") (pintype "passive"))
      (node (ref "L1") (pin "2") (pinfunction "2_2") (pintype "passive"))
      (node (ref "U3") (pin "8") (pinfunction "SW_8") (pintype "output"))
    )
    (net (code "56") (name "Net-(X2B-1)") (class "Default")
      (node (ref "R3") (pin "1") (pinfunction "1_1") (pintype "passive"))
      (node (ref "X2") (pin "2") (pinfunction "1_2") (pintype "passive"))
    )
    (net (code "57") (name "Net-(X2C-1)") (class "Default")
      (node (ref "R5") (pin "1") (pinfunction "1_1") (pintype "passive"))
      (node (ref "X2") (pin "3") (pinfunction "1_3") (pintype "passive"))
    )
    (net (code "58") (name "unconnected-(5VPWR-Pad1)") (class "Default")
      (node (ref "5VPWR") (pin "1") (pinfunction "1_1") (pintype "passive"))
    )
    (net (code "59") (name "unconnected-(ESC_1-Pad2)") (class "Default")
      (node (ref "ESC_1") (pin "2") (pinfunction "2_2") (pintype "passive"))
    )
    (net (code "60") (name "unconnected-(ESC_2-Pad2)") (class "Default")
      (node (ref "ESC_2") (pin "2") (pinfunction "2_2") (pintype "passive"))
    )
    (net (code "61") (name "unconnected-(ESC_3-Pad2)") (class "Default")
      (node (ref "ESC_3") (pin "2") (pinfunction "2_2") (pintype "passive"))
    )
    (net (code "62") (name "unconnected-(ESC_4-Pad2)") (class "Default")
      (node (ref "ESC_4") (pin "2") (pinfunction "2_2") (pintype "passive"))
    )
    (net (code "63") (name "unconnected-(IC1-NC_2-Pad7)") (class "Default")
      (node (ref "IC1") (pin "7") (pinfunction "NC_2_7") (pintype "bidirectional"))
    )
    (net (code "64") (name "unconnected-(PRESSURE-Pad4)") (class "Default")
      (node (ref "PRESSURE") (pin "4") (pinfunction "4_4") (pintype "passive"))
    )
    (net (code "65") (name "unconnected-(U1A-PA0{slash}WKUP-Pad14)") (class "Default")
      (node (ref "U1") (pin "14") (pinfunction "PA0/WKUP_14") (pintype "bidirectional"))
    )
    (net (code "66") (name "unconnected-(U1A-PA8-Pad41)") (class "Default")
      (node (ref "U1") (pin "41") (pinfunction "PA8_41") (pintype "bidirectional"))
    )
    (net (code "67") (name "unconnected-(U1A-PB5-Pad57)") (class "Default")
      (node (ref "U1") (pin "57") (pinfunction "PB5_57") (pintype "bidirectional"))
    )
    (net (code "68") (name "unconnected-(U1A-PB10-Pad29)") (class "Default")
      (node (ref "U1") (pin "29") (pinfunction "PB10_29") (pintype "bidirectional"))
    )
    (net (code "69") (name "unconnected-(U1A-PB11-Pad30)") (class "Default")
      (node (ref "U1") (pin "30") (pinfunction "PB11_30") (pintype "bidirectional"))
    )
    (net (code "70") (name "unconnected-(U1A-PB13-Pad34)") (class "Default")
      (node (ref "U1") (pin "34") (pinfunction "PB13_34") (pintype "bidirectional"))
    )
    (net (code "71") (name "unconnected-(U1A-PC0-Pad8)") (class "Default")
      (node (ref "U1") (pin "8") (pinfunction "PC0_8") (pintype "bidirectional"))
    )
    (net (code "72") (name "unconnected-(U1A-PC3-Pad11)") (class "Default")
      (node (ref "U1") (pin "11") (pinfunction "PC3_11") (pintype "bidirectional"))
    )
    (net (code "73") (name "unconnected-(U1A-PC5-Pad25)") (class "Default")
      (node (ref "U1") (pin "25") (pinfunction "PC5_25") (pintype "bidirectional"))
    )
    (net (code "74") (name "unconnected-(U1A-PC8-Pad39)") (class "Default")
      (node (ref "U1") (pin "39") (pinfunction "PC8_39") (pintype "bidirectional"))
    )
    (net (code "75") (name "unconnected-(U1A-PC9-Pad40)") (class "Default")
      (node (ref "U1") (pin "40") (pinfunction "PC9_40") (pintype "bidirectional"))
    )
    (net (code "76") (name "unconnected-(U1A-PC10-Pad51)") (class "Default")
      (node (ref "U1") (pin "51") (pinfunction "PC10_51") (pintype "bidirectional"))
    )
    (net (code "77") (name "unconnected-(U1A-PC11-Pad52)") (class "Default")
      (node (ref "U1") (pin "52") (pinfunction "PC11_52") (pintype "bidirectional"))
    )
    (net (code "78") (name "unconnected-(U1A-PC12-Pad53)") (class "Default")
      (node (ref "U1") (pin "53") (pinfunction "PC12_53") (pintype "bidirectional"))
    )
    (net (code "79") (name "unconnected-(U1A-PC14{slash}OSC32_IN-Pad3)") (class "Default")
      (node (ref "U1") (pin "3") (pinfunction "PC14/OSC32_IN_3") (pintype "bidirectional"))
    )
    (net (code "80") (name "unconnected-(U1A-PC15{slash}OSC32_OUT-Pad4)") (class "Default")
      (node (ref "U1") (pin "4") (pinfunction "PC15/OSC32_OUT_4") (pintype "bidirectional"))
    )
    (net (code "81") (name "unconnected-(U2A-AUX_CL-Pad7)") (class "Default")
      (node (ref "U2") (pin "7") (pinfunction "AUX_CL_7") (pintype "passive"))
    )
    (net (code "82") (name "unconnected-(U2A-AUX_DA-Pad21)") (class "Default")
      (node (ref "U2") (pin "21") (pinfunction "AUX_DA_21") (pintype "passive"))
    )
    (net (code "83") (name "unconnected-(U2A-INT1-Pad12)") (class "Default")
      (node (ref "U2") (pin "12") (pinfunction "INT1_12") (pintype "output"))
    )
    (net (code "84") (name "unconnected-(U2B-NC-Pad17)") (class "Default")
      (node (ref "U2") (pin "17") (pinfunction "NC_17") (pintype "no_connect"))
    )
    (net (code "85") (name "unconnected-(U2B-NC_2-Pad1)") (class "Default")
      (node (ref "U2") (pin "1") (pinfunction "NC_2_1") (pintype "no_connect"))
    )
    (net (code "86") (name "unconnected-(U2B-NC_3-Pad2)") (class "Default")
      (node (ref "U2") (pin "2") (pinfunction "NC_3_2") (pintype "no_connect"))
    )
    (net (code "87") (name "unconnected-(U2B-NC_4-Pad3)") (class "Default")
      (node (ref "U2") (pin "3") (pinfunction "NC_4_3") (pintype "no_connect"))
    )
    (net (code "88") (name "unconnected-(U2B-NC_5-Pad4)") (class "Default")
      (node (ref "U2") (pin "4") (pinfunction "NC_5_4") (pintype "no_connect"))
    )
    (net (code "89") (name "unconnected-(U2B-NC_6-Pad5)") (class "Default")
      (node (ref "U2") (pin "5") (pinfunction "NC_6_5") (pintype "no_connect"))
    )
    (net (code "90") (name "unconnected-(U2B-NC_7-Pad6)") (class "Default")
      (node (ref "U2") (pin "6") (pinfunction "NC_7_6") (pintype "no_connect"))
    )
    (net (code "91") (name "unconnected-(U2B-NC_8-Pad14)") (class "Default")
      (node (ref "U2") (pin "14") (pinfunction "NC_8_14") (pintype "no_connect"))
    )
    (net (code "92") (name "unconnected-(U2B-NC_9-Pad15)") (class "Default")
      (node (ref "U2") (pin "15") (pinfunction "NC_9_15") (pintype "no_connect"))
    )
    (net (code "93") (name "unconnected-(U2B-NC_10-Pad16)") (class "Default")
      (node (ref "U2") (pin "16") (pinfunction "NC_10_16") (pintype "no_connect"))
    )
    (net (code "94") (name "unconnected-(U2B-RESV-Pad19)") (class "Default")
      (node (ref "U2") (pin "19") (pinfunction "RESV_19") (pintype "no_connect"))
    )
    (net (code "95") (name "unconnected-(U3-NC-Pad6)") (class "Default")
      (node (ref "U3") (pin "6") (pinfunction "NC_6") (pintype "no_connect"))
    )
    (net (code "96") (name "unconnected-(U5-P4-Pad4)") (class "Default")
      (node (ref "U5") (pin "4") (pinfunction "P4_4") (pintype "bidirectional"))
    )
    (net (code "97") (name "unconnected-(X1-Pad4)") (class "Default")
      (node (ref "X1") (pin "4") (pinfunction "4_4") (pintype "passive"))
    )
  )
)
